# VerticalPCBConnection.net
KiCad netlist of a schematic drawn in Altium Designer
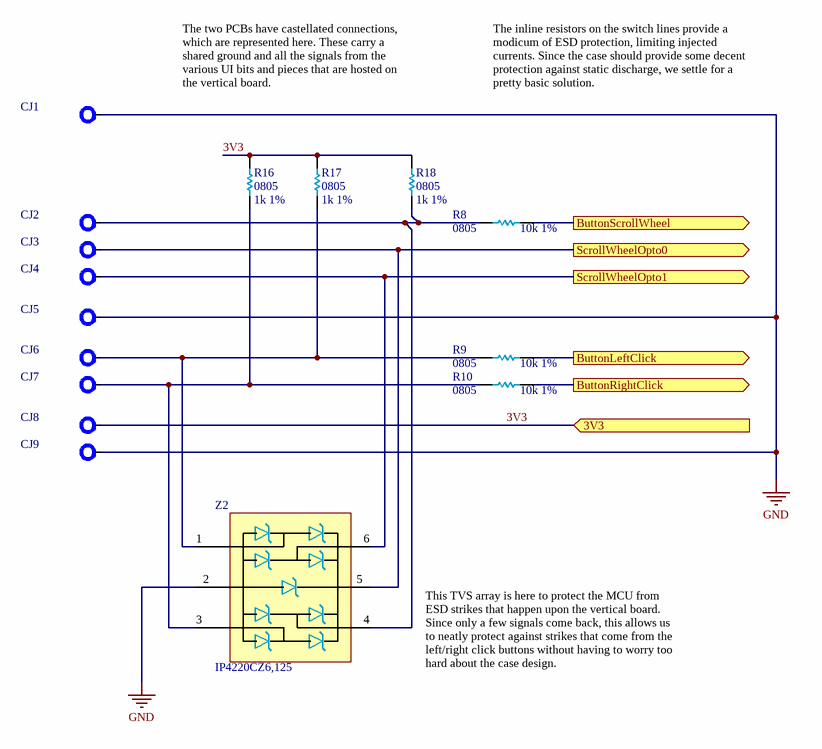
[diagram p0: VerticalPCBConnection.SchDoc]

(export (version "E")
  (design (tool "Eeschema 10.0.6"))
  (components
    (comp (ref "CJ1")
      (value "PCBJointCastellationJoint")
      (footprint "PCBJoint")
      (description "Pad for soldering a castellated PCB edge. Easy way to join two PCBs together.")
      (libsource (lib "PCBFeatures") (part "PCBJoint"))
    )
    (comp (ref "CJ2")
      (value "PCBJointCastellationJoint")
      (footprint "PCBJoint")
      (description "Pad for soldering a castellated PCB edge. Easy way to join two PCBs together.")
      (libsource (lib "PCBFeatures") (part "PCBJoint"))
    )
    (comp (ref "CJ3")
      (value "PCBJointCastellationJoint")
      (footprint "PCBJoint")
      (description "Pad for soldering a castellated PCB edge. Easy way to join two PCBs together.")
      (libsource (lib "PCBFeatures") (part "PCBJoint"))
    )
    (comp (ref "CJ4")
      (value "PCBJointCastellationJoint")
      (footprint "PCBJoint")
      (description "Pad for soldering a castellated PCB edge. Easy way to join two PCBs together.")
      (libsource (lib "PCBFeatures") (part "PCBJoint"))
    )
    (comp (ref "CJ5")
      (value "PCBJointCastellationJoint")
      (footprint "PCBJoint")
      (description "Pad for soldering a castellated PCB edge. Easy way to join two PCBs together.")
      (libsource (lib "PCBFeatures") (part "PCBJoint"))
    )
    (comp (ref "CJ6")
      (value "PCBJointCastellationJoint")
      (footprint "PCBJoint")
      (description "Pad for soldering a castellated PCB edge. Easy way to join two PCBs together.")
      (libsource (lib "PCBFeatures") (part "PCBJoint"))
    )
    (comp (ref "CJ7")
      (value "PCBJointCastellationJoint")
      (footprint "PCBJoint")
      (description "Pad for soldering a castellated PCB edge. Easy way to join two PCBs together.")
      (libsource (lib "PCBFeatures") (part "PCBJoint"))
    )
    (comp (ref "CJ8")
      (value "PCBJointCastellationJoint")
      (footprint "PCBJoint")
      (description "Pad for soldering a castellated PCB edge. Easy way to join two PCBs together.")
      (libsource (lib "PCBFeatures") (part "PCBJoint"))
    )
    (comp (ref "CJ9")
      (value "PCBJointCastellationJoint")
      (footprint "PCBJoint")
      (description "Pad for soldering a castellated PCB edge. Easy way to join two PCBs together.")
      (libsource (lib "PCBFeatures") (part "PCBJoint"))
    )
    (comp (ref "R8")
      (value "0805")
      (footprint "0805")
      (description "Chip resistor")
      (fields (field (name "ALTIUM_VALUE") "10k 1%"))
      (libsource (lib "Chip_Passives") (part "Res 10k 1% 0805"))
    )
    (comp (ref "R9")
      (value "0805")
      (footprint "0805")
      (description "Chip resistor")
      (fields (field (name "ALTIUM_VALUE") "10k 1%"))
      (libsource (lib "Chip_Passives") (part "Res 10k 1% 0805"))
    )
    (comp (ref "R10")
      (value "0805")
      (footprint "0805")
      (description "Chip resistor")
      (fields (field (name "ALTIUM_VALUE") "10k 1%"))
      (libsource (lib "Chip_Passives") (part "Res 10k 1% 0805"))
    )
    (comp (ref "R16")
      (value "0805")
      (footprint "0805")
      (description "Chip resistor, 1/8W 100PPM")
      (fields (field (name "ALTIUM_VALUE") "1k 1%"))
      (libsource (lib "Chip_Passives") (part "Res 1k 1% 0805"))
    )
    (comp (ref "R17")
      (value "0805")
      (footprint "0805")
      (description "Chip resistor, 1/8W 100PPM")
      (fields (field (name "ALTIUM_VALUE") "1k 1%"))
      (libsource (lib "Chip_Passives") (part "Res 1k 1% 0805"))
    )
    (comp (ref "R18")
      (value "0805")
      (footprint "0805")
      (description "Chip resistor, 1/8W 100PPM")
      (fields (field (name "ALTIUM_VALUE") "1k 1%"))
      (libsource (lib "Chip_Passives") (part "Res 1k 1% 0805"))
    )
    (comp (ref "Z2")
      (value "IP4220CZ6,125")
      (footprint "PESD3V3S4UD - SOT95P275X110-6N")
      (description "TVS DIODE 5.5V 6TSOP (Low capacitance, USB)")
      (libsource (lib "Diodes") (part "IP4220CZ6,125"))
    )
  )
  (nets
    (net (code "1") (name "/3V3") (class "Default")
      (node (ref "CJ8") (pin "1") (pinfunction "1_1") (pintype "passive"))
      (node (ref "R16") (pin "2") (pinfunction "2_2") (pintype "passive"))
      (node (ref "R17") (pin "2") (pinfunction "2_2") (pintype "passive"))
      (node (ref "R18") (pin "2") (pinfunction "2_2") (pintype "passive"))
    )
    (net (code "2") (name "/ButtonLeftClick") (class "Default")
      (node (ref "R9") (pin "2") (pinfunction "2_2") (pintype "passive"))
    )
    (net (code "3") (name "/ButtonRightClick") (class "Default")
      (node (ref "R10") (pin "2") (pinfunction "2_2") (pintype "passive"))
    )
    (net (code "4") (name "/ButtonScrollWheel") (class "Default")
      (node (ref "R8") (pin "2") (pinfunction "2_2") (pintype "passive"))
    )
    (net (code "5") (name "/ScrollWheelOpto0") (class "Default")
      (node (ref "CJ3") (pin "1") (pinfunction "1_1") (pintype "passive"))
      (node (ref "Z2") (pin "5") (pinfunction "5_5") (pintype "passive"))
    )
    (net (code "6") (name "/ScrollWheelOpto1") (class "Default")
      (node (ref "CJ4") (pin "1") (pinfunction "1_1") (pintype "passive"))
      (node (ref "Z2") (pin "6") (pinfunction "6_6") (pintype "passive"))
    )
    (net (code "7") (name "GND") (class "Default")
      (node (ref "CJ1") (pin "1") (pinfunction "1_1") (pintype "passive"))
      (node (ref "CJ5") (pin "1") (pinfunction "1_1") (pintype "passive"))
      (node (ref "CJ9") (pin "1") (pinfunction "1_1") (pintype "passive"))
      (node (ref "Z2") (pin "2") (pinfunction "2_2") (pintype "passive"))
    )
    (net (code "8") (name "Net-(CJ2-Pad1)") (class "Default")
      (node (ref "CJ2") (pin "1") (pinfunction "1_1") (pintype "passive"))
      (node (ref "R18") (pin "1") (pinfunction "1_1") (pintype "passive"))
      (node (ref "R8") (pin "1") (pinfunction "1_1") (pintype "passive"))
      (node (ref "Z2") (pin "4") (pinfunction "4_4") (pintype "passive"))
    )
    (net (code "9") (name "Net-(CJ6-Pad1)") (class "Default")
      (node (ref "CJ6") (pin "1") (pinfunction "1_1") (pintype "passive"))
      (node (ref "R17") (pin "1") (pinfunction "1_1") (pintype "passive"))
      (node (ref "R9") (pin "1") (pinfunction "1_1") (pintype "passive"))
      (node (ref "Z2") (pin "1") (pinfunction "1_1") (pintype "passive"))
    )
    (net (code "10") (name "Net-(CJ7-Pad1)") (class "Default")
      (node (ref "CJ7") (pin "1") (pinfunction "1_1") (pintype "passive"))
      (node (ref "R10") (pin "1") (pinfunction "1_1") (pintype "passive"))
      (node (ref "R16") (pin "1") (pinfunction "1_1") (pintype "passive"))
      (node (ref "Z2") (pin "3") (pinfunction "3_3") (pintype "passive"))
    )
  )
)
